# utrak.net
KiCad netlist of a schematic drawn in EAGLE
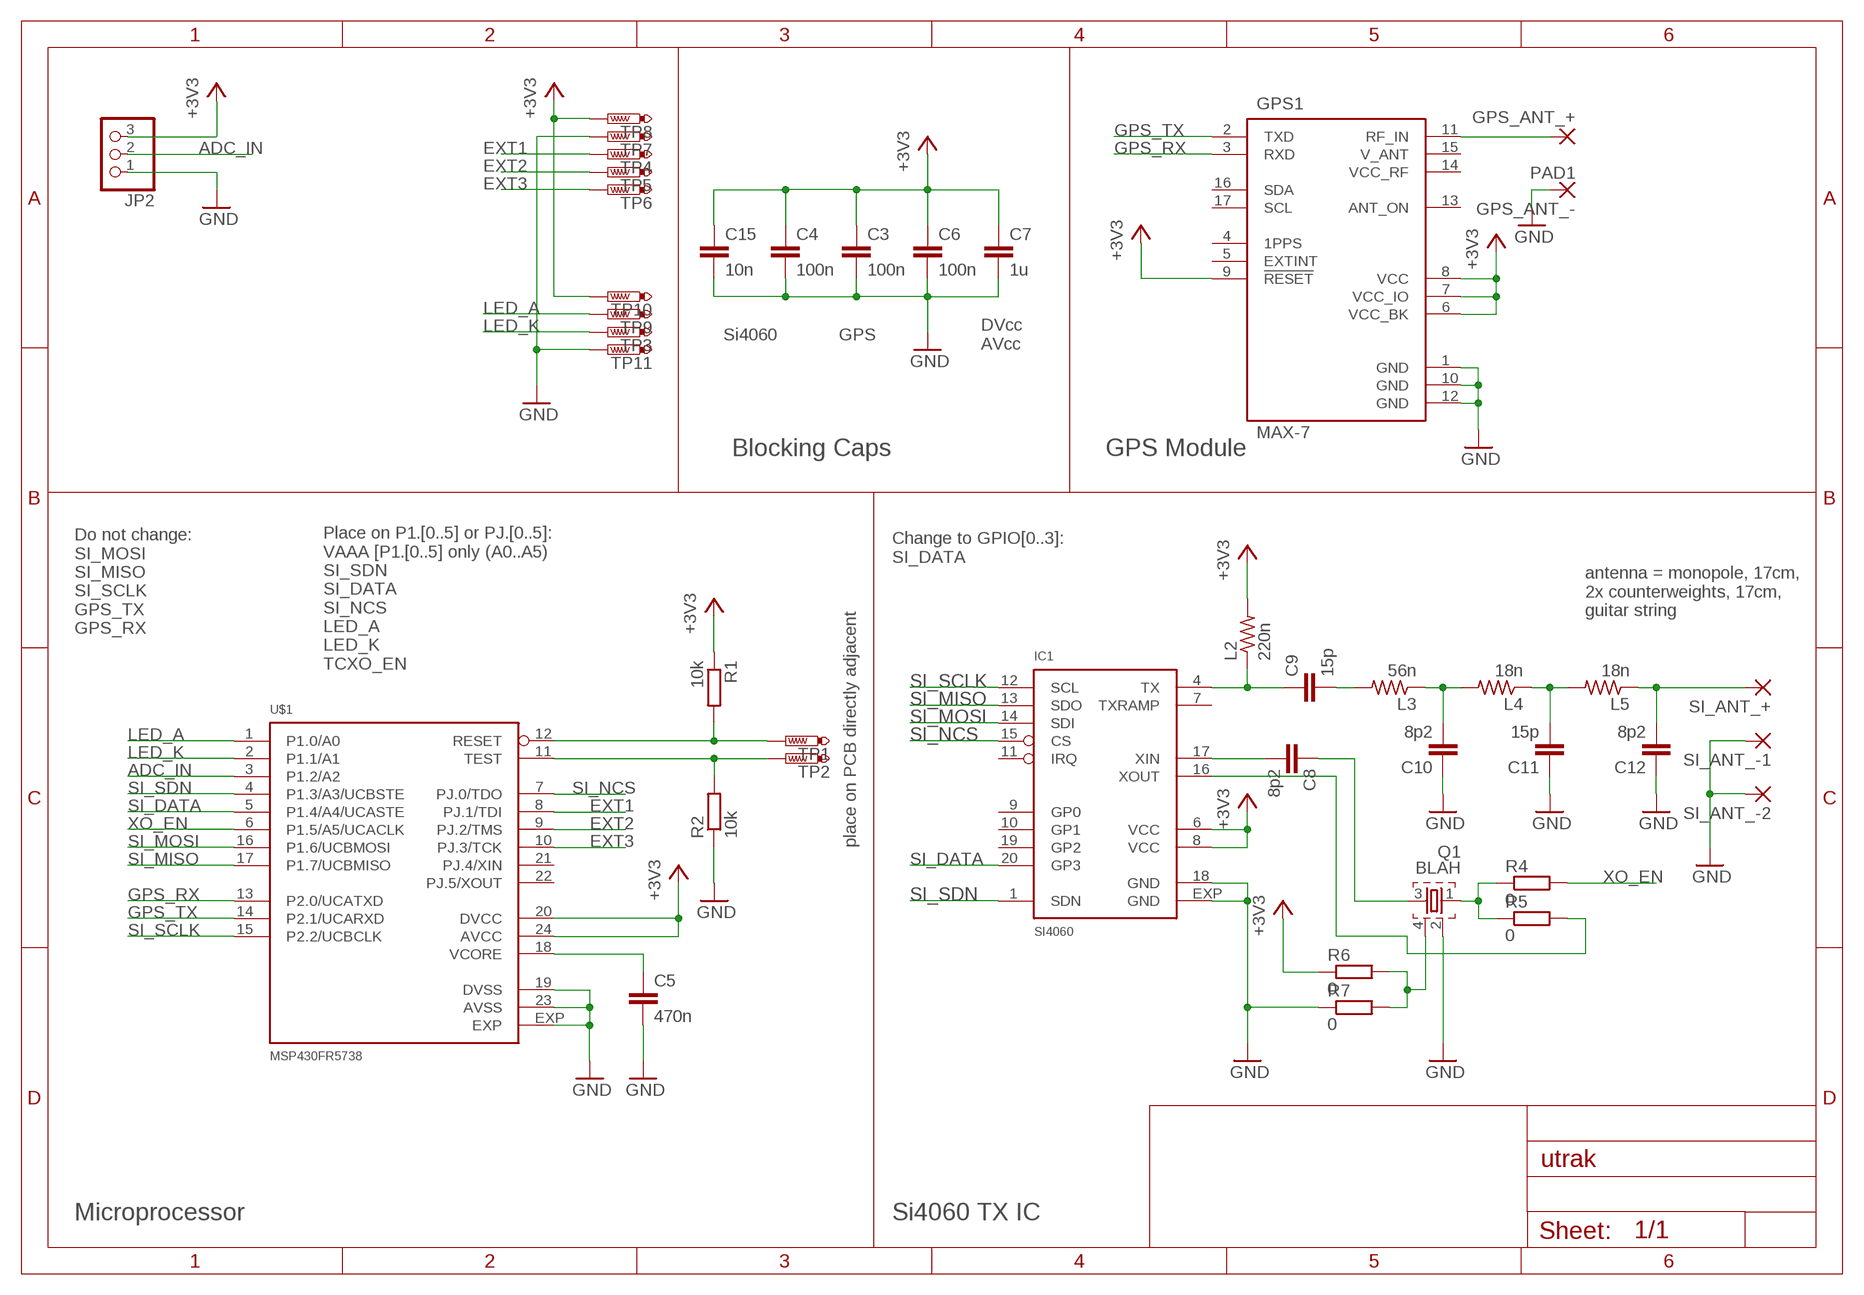
[diagram p0: schematic, sheet 1]

(export (version "E")
  (design (tool "Eeschema 10.0.6"))
  (components
    (comp (ref "C3")
      (value "100n")
      (footprint "eagle-import:C0603")
      (libsource (lib "eagle-import") (part "C-EUC0603"))
    )
    (comp (ref "C4")
      (value "100n")
      (footprint "eagle-import:C0603")
      (libsource (lib "eagle-import") (part "C-EUC0603"))
    )
    (comp (ref "C5")
      (value "470n")
      (footprint "eagle-import:C0805")
      (libsource (lib "eagle-import") (part "C-EUC0805"))
    )
    (comp (ref "C6")
      (value "100n")
      (footprint "eagle-import:C0603")
      (libsource (lib "eagle-import") (part "C-EUC0603"))
    )
    (comp (ref "C7")
      (value "1u")
      (footprint "eagle-import:C0603")
      (libsource (lib "eagle-import") (part "C-EUC0603"))
    )
    (comp (ref "C8")
      (value "8p2")
      (footprint "eagle-import:C0402")
      (libsource (lib "eagle-import") (part "C-EUC0402"))
    )
    (comp (ref "C9")
      (value "15p")
      (footprint "eagle-import:C0603")
      (libsource (lib "eagle-import") (part "C-EUC0603"))
    )
    (comp (ref "C10")
      (value "8p2")
      (footprint "eagle-import:C0603")
      (libsource (lib "eagle-import") (part "C-EUC0603"))
    )
    (comp (ref "C11")
      (value "15p")
      (footprint "eagle-import:C0603K")
      (libsource (lib "eagle-import") (part "C-EUC0603K"))
    )
    (comp (ref "C12")
      (value "8p2")
      (footprint "eagle-import:C0603")
      (libsource (lib "eagle-import") (part "C-EUC0603"))
    )
    (comp (ref "C15")
      (value "10n")
      (footprint "eagle-import:C0603")
      (libsource (lib "eagle-import") (part "C-EUC0603"))
    )
    (comp (ref "GPS1")
      (value "MAX-7")
      (footprint "eagle-import:UBLOX-7")
      (libsource (lib "eagle-import") (part "MAX-7"))
    )
    (comp (ref "GPS_ANT_+")
      (value "SMD2")
      (footprint "eagle-import:SMD1,27-2,54")
      (libsource (lib "eagle-import") (part "SMD2"))
    )
    (comp (ref "GPS_ANT_-")
      (value "PAD1")
      (footprint "eagle-import:SMD1,27-2,0")
      (libsource (lib "eagle-import") (part "PAD1"))
    )
    (comp (ref "IC1")
      (value "SI4060")
      (footprint "eagle-import:QFN20")
      (libsource (lib "eagle-import") (part "SI4060"))
    )
    (comp (ref "JP2")
      (value "PINHD-1X3")
      (footprint "eagle-import:1X03")
      (libsource (lib "eagle-import") (part "PINHD-1X3"))
    )
    (comp (ref "L2")
      (value "220n")
      (footprint "eagle-import:R0603")
      (libsource (lib "eagle-import") (part "R-US_R0603"))
    )
    (comp (ref "L3")
      (value "56n")
      (footprint "eagle-import:R0603")
      (libsource (lib "eagle-import") (part "R-US_R0603"))
    )
    (comp (ref "L4")
      (value "18n")
      (footprint "eagle-import:R0603")
      (libsource (lib "eagle-import") (part "R-US_R0603"))
    )
    (comp (ref "L5")
      (value "18n")
      (footprint "eagle-import:R0603")
      (libsource (lib "eagle-import") (part "R-US_R0603"))
    )
    (comp (ref "Q1")
      (value "BLAH")
      (footprint "eagle-import:CTS406")
      (libsource (lib "eagle-import") (part "BLAH"))
    )
    (comp (ref "R1")
      (value "10k")
      (footprint "eagle-import:R0402")
      (libsource (lib "eagle-import") (part "R-EU_R0402"))
    )
    (comp (ref "R2")
      (value "10k")
      (footprint "eagle-import:R0402")
      (libsource (lib "eagle-import") (part "R-EU_R0402"))
    )
    (comp (ref "R4")
      (value "0")
      (footprint "eagle-import:R0402")
      (libsource (lib "eagle-import") (part "R-EU_R0402"))
    )
    (comp (ref "R5")
      (value "0")
      (footprint "eagle-import:R0402")
      (libsource (lib "eagle-import") (part "R-EU_R0402"))
    )
    (comp (ref "R6")
      (value "0")
      (footprint "eagle-import:R0402")
      (libsource (lib "eagle-import") (part "R-EU_R0402"))
    )
    (comp (ref "R7")
      (value "0")
      (footprint "eagle-import:R0402")
      (libsource (lib "eagle-import") (part "R-EU_R0402"))
    )
    (comp (ref "SI_ANT_+")
      (value "SMD2")
      (footprint "eagle-import:SMD1,27-2,54")
      (libsource (lib "eagle-import") (part "SMD2"))
    )
    (comp (ref "SI_ANT_-1")
      (value "SMD2")
      (footprint "eagle-import:SMD1,27-2,54")
      (libsource (lib "eagle-import") (part "SMD2"))
    )
    (comp (ref "SI_ANT_-2")
      (value "SMD2")
      (footprint "eagle-import:SMD1,27-2,54")
      (libsource (lib "eagle-import") (part "SMD2"))
    )
    (comp (ref "TP1")
      (value "PTR1TP07R")
      (footprint "eagle-import:TP07R")
      (libsource (lib "eagle-import") (part "PTR1TP07R"))
    )
    (comp (ref "TP2")
      (value "PTR1TP07R")
      (footprint "eagle-import:TP07R")
      (libsource (lib "eagle-import") (part "PTR1TP07R"))
    )
    (comp (ref "TP3")
      (value "PTR1TP07R")
      (footprint "eagle-import:TP07R")
      (libsource (lib "eagle-import") (part "PTR1TP07R"))
    )
    (comp (ref "TP4")
      (value "PTR1TP07R")
      (footprint "eagle-import:TP07R")
      (libsource (lib "eagle-import") (part "PTR1TP07R"))
    )
    (comp (ref "TP5")
      (value "PTR1TP07R")
      (footprint "eagle-import:TP07R")
      (libsource (lib "eagle-import") (part "PTR1TP07R"))
    )
    (comp (ref "TP6")
      (value "PTR1TP07R")
      (footprint "eagle-import:TP07R")
      (libsource (lib "eagle-import") (part "PTR1TP07R"))
    )
    (comp (ref "TP7")
      (value "PTR1TP07R")
      (footprint "eagle-import:TP07R")
      (libsource (lib "eagle-import") (part "PTR1TP07R"))
    )
    (comp (ref "TP8")
      (value "PTR1TP07R")
      (footprint "eagle-import:TP07R")
      (libsource (lib "eagle-import") (part "PTR1TP07R"))
    )
    (comp (ref "TP9")
      (value "PTR1TP07R")
      (footprint "eagle-import:TP07R")
      (libsource (lib "eagle-import") (part "PTR1TP07R"))
    )
    (comp (ref "TP10")
      (value "PTR1TP07R")
      (footprint "eagle-import:TP07R")
      (libsource (lib "eagle-import") (part "PTR1TP07R"))
    )
    (comp (ref "TP11")
      (value "PTR1TP07R")
      (footprint "eagle-import:TP07R")
      (libsource (lib "eagle-import") (part "PTR1TP07R"))
    )
    (comp (ref "U$1")
      (value "MSP430FR5738")
      (footprint "eagle-import:QFN24-4X4")
      (libsource (lib "eagle-import") (part "MSP430FR5738"))
    )
  )
  (nets
    (net (code "1") (name "+3V3") (class "Default")
      (node (ref "C15") (pin "1") (pinfunction "1_1") (pintype "passive"))
      (node (ref "C3") (pin "1") (pinfunction "1_1") (pintype "passive"))
      (node (ref "C4") (pin "1") (pinfunction "1_1") (pintype "passive"))
      (node (ref "C6") (pin "1") (pinfunction "1_1") (pintype "passive"))
      (node (ref "C7") (pin "1") (pinfunction "1_1") (pintype "passive"))
      (node (ref "GPS1") (pin "6") (pinfunction "VCC_BK_6") (pintype "power_in"))
      (node (ref "GPS1") (pin "7") (pinfunction "VCC_IO_7") (pintype "power_in"))
      (node (ref "GPS1") (pin "8") (pinfunction "VCC_8") (pintype "power_in"))
      (node (ref "GPS1") (pin "9") (pinfunction "~{RESET}_9") (pintype "bidirectional"))
      (node (ref "IC1") (pin "6") (pinfunction "VCC_6") (pintype "power_in"))
      (node (ref "IC1") (pin "8") (pinfunction "VCC_8") (pintype "power_in"))
      (node (ref "JP2") (pin "3") (pinfunction "3_3") (pintype "passive"))
      (node (ref "L2") (pin "2") (pinfunction "2_2") (pintype "passive"))
      (node (ref "R1") (pin "1") (pinfunction "1_1") (pintype "passive"))
      (node (ref "R6") (pin "1") (pinfunction "1_1") (pintype "passive"))
      (node (ref "TP10") (pin "TP") (pinfunction "TP_TP") (pintype "input"))
      (node (ref "TP8") (pin "TP") (pinfunction "TP_TP") (pintype "input"))
      (node (ref "U$1") (pin "20") (pinfunction "DVCC_20") (pintype "power_in"))
      (node (ref "U$1") (pin "24") (pinfunction "AVCC_24") (pintype "power_in"))
    )
    (net (code "2") (name "/ADC_IN") (class "Default")
      (node (ref "JP2") (pin "2") (pinfunction "2_2") (pintype "passive"))
      (node (ref "U$1") (pin "3") (pinfunction "P1.2/A2_3") (pintype "bidirectional"))
    )
    (net (code "3") (name "/EXT1") (class "Default")
      (node (ref "TP4") (pin "TP") (pinfunction "TP_TP") (pintype "input"))
      (node (ref "U$1") (pin "8") (pinfunction "PJ.1/TDI_8") (pintype "bidirectional"))
    )
    (net (code "4") (name "/EXT2") (class "Default")
      (node (ref "TP5") (pin "TP") (pinfunction "TP_TP") (pintype "input"))
      (node (ref "U$1") (pin "9") (pinfunction "PJ.2/TMS_9") (pintype "bidirectional"))
    )
    (net (code "5") (name "/EXT3") (class "Default")
      (node (ref "TP6") (pin "TP") (pinfunction "TP_TP") (pintype "input"))
      (node (ref "U$1") (pin "10") (pinfunction "PJ.3/TCK_10") (pintype "bidirectional"))
    )
    (net (code "6") (name "/GPS_RX") (class "Default")
      (node (ref "GPS1") (pin "3") (pinfunction "RXD_3") (pintype "bidirectional"))
      (node (ref "U$1") (pin "13") (pinfunction "P2.0/UCATXD_13") (pintype "bidirectional"))
    )
    (net (code "7") (name "/GPS_TX") (class "Default")
      (node (ref "GPS1") (pin "2") (pinfunction "TXD_2") (pintype "bidirectional"))
      (node (ref "U$1") (pin "14") (pinfunction "P2.1/UCARXD_14") (pintype "bidirectional"))
    )
    (net (code "8") (name "/LED_A") (class "Default")
      (node (ref "TP9") (pin "TP") (pinfunction "TP_TP") (pintype "input"))
      (node (ref "U$1") (pin "1") (pinfunction "P1.0/A0_1") (pintype "bidirectional"))
    )
    (net (code "9") (name "/LED_K") (class "Default")
      (node (ref "TP3") (pin "TP") (pinfunction "TP_TP") (pintype "input"))
      (node (ref "U$1") (pin "2") (pinfunction "P1.1/A1_2") (pintype "bidirectional"))
    )
    (net (code "10") (name "/SI_DATA") (class "Default")
      (node (ref "IC1") (pin "20") (pinfunction "GP3_20") (pintype "bidirectional"))
      (node (ref "U$1") (pin "5") (pinfunction "P1.4/A4/UCASTE_5") (pintype "bidirectional"))
    )
    (net (code "11") (name "/SI_MISO") (class "Default")
      (node (ref "IC1") (pin "13") (pinfunction "SDO_13") (pintype "bidirectional"))
      (node (ref "U$1") (pin "17") (pinfunction "P1.7/UCBMISO_17") (pintype "bidirectional"))
    )
    (net (code "12") (name "/SI_MOSI") (class "Default")
      (node (ref "IC1") (pin "14") (pinfunction "SDI_14") (pintype "bidirectional"))
      (node (ref "U$1") (pin "16") (pinfunction "P1.6/UCBMOSI_16") (pintype "bidirectional"))
    )
    (net (code "13") (name "/SI_NCS") (class "Default")
      (node (ref "IC1") (pin "15") (pinfunction "CS_15") (pintype "bidirectional"))
      (node (ref "U$1") (pin "7") (pinfunction "PJ.0/TDO_7") (pintype "bidirectional"))
    )
    (net (code "14") (name "/SI_SCLK") (class "Default")
      (node (ref "IC1") (pin "12") (pinfunction "SCL_12") (pintype "bidirectional"))
      (node (ref "U$1") (pin "15") (pinfunction "P2.2/UCBCLK_15") (pintype "bidirectional"))
    )
    (net (code "15") (name "/SI_SDN") (class "Default")
      (node (ref "IC1") (pin "1") (pinfunction "SDN_1") (pintype "bidirectional"))
      (node (ref "U$1") (pin "4") (pinfunction "P1.3/A3/UCBSTE_4") (pintype "bidirectional"))
    )
    (net (code "16") (name "/XO_EN") (class "Default")
      (node (ref "R4") (pin "2") (pinfunction "2_2") (pintype "passive"))
      (node (ref "U$1") (pin "6") (pinfunction "P1.5/A5/UCACLK_6") (pintype "bidirectional"))
    )
    (net (code "17") (name "GND") (class "Default")
      (node (ref "C10") (pin "1") (pinfunction "1_1") (pintype "passive"))
      (node (ref "C11") (pin "1") (pinfunction "1_1") (pintype "passive"))
      (node (ref "C12") (pin "1") (pinfunction "1_1") (pintype "passive"))
      (node (ref "C15") (pin "2") (pinfunction "2_2") (pintype "passive"))
      (node (ref "C3") (pin "2") (pinfunction "2_2") (pintype "passive"))
      (node (ref "C4") (pin "2") (pinfunction "2_2") (pintype "passive"))
      (node (ref "C5") (pin "2") (pinfunction "2_2") (pintype "passive"))
      (node (ref "C6") (pin "2") (pinfunction "2_2") (pintype "passive"))
      (node (ref "C7") (pin "2") (pinfunction "2_2") (pintype "passive"))
      (node (ref "GPS1") (pin "1") (pinfunction "GND_1") (pintype "power_in"))
      (node (ref "GPS1") (pin "10") (pinfunction "GND_10") (pintype "power_in"))
      (node (ref "GPS1") (pin "12") (pinfunction "GND_12") (pintype "power_in"))
      (node (ref "GPS_ANT_-") (pin "P$1") (pinfunction "P_P$1") (pintype "passive"))
      (node (ref "IC1") (pin "18") (pinfunction "GND_18") (pintype "power_in"))
      (node (ref "IC1") (pin "EXP") (pinfunction "GND_EXP") (pintype "power_in"))
      (node (ref "JP2") (pin "1") (pinfunction "1_1") (pintype "passive"))
      (node (ref "Q1") (pin "2") (pinfunction "2_2") (pintype "passive"))
      (node (ref "R2") (pin "1") (pinfunction "1_1") (pintype "passive"))
      (node (ref "R7") (pin "1") (pinfunction "1_1") (pintype "passive"))
      (node (ref "SI_ANT_-1") (pin "1") (pinfunction "P_1") (pintype "passive"))
      (node (ref "SI_ANT_-2") (pin "1") (pinfunction "P_1") (pintype "passive"))
      (node (ref "TP11") (pin "TP") (pinfunction "TP_TP") (pintype "input"))
      (node (ref "TP7") (pin "TP") (pinfunction "TP_TP") (pintype "input"))
      (node (ref "U$1") (pin "19") (pinfunction "DVSS_19") (pintype "power_in"))
      (node (ref "U$1") (pin "23") (pinfunction "AVSS_23") (pintype "power_in"))
      (node (ref "U$1") (pin "EXP") (pinfunction "EXP_EXP") (pintype "power_in"))
    )
    (net (code "18") (name "Net-(C8-Pad1)") (class "Default")
      (node (ref "C8") (pin "1") (pinfunction "1_1") (pintype "passive"))
      (node (ref "Q1") (pin "3") (pinfunction "3_3") (pintype "passive"))
    )
    (net (code "19") (name "Net-(C9-Pad2)") (class "Default")
      (node (ref "C9") (pin "2") (pinfunction "2_2") (pintype "passive"))
      (node (ref "L3") (pin "2") (pinfunction "2_2") (pintype "passive"))
    )
    (net (code "20") (name "Net-(C10-Pad2)") (class "Default")
      (node (ref "C10") (pin "2") (pinfunction "2_2") (pintype "passive"))
      (node (ref "L3") (pin "1") (pinfunction "1_1") (pintype "passive"))
      (node (ref "L4") (pin "2") (pinfunction "2_2") (pintype "passive"))
    )
    (net (code "21") (name "Net-(C11-Pad2)") (class "Default")
      (node (ref "C11") (pin "2") (pinfunction "2_2") (pintype "passive"))
      (node (ref "L4") (pin "1") (pinfunction "1_1") (pintype "passive"))
      (node (ref "L5") (pin "2") (pinfunction "2_2") (pintype "passive"))
    )
    (net (code "22") (name "Net-(GPS1-RF_IN)") (class "Default")
      (node (ref "GPS1") (pin "11") (pinfunction "RF_IN_11") (pintype "bidirectional"))
      (node (ref "GPS_ANT_+") (pin "1") (pinfunction "P_1") (pintype "passive"))
    )
    (net (code "23") (name "Net-(IC1-TX)") (class "Default")
      (node (ref "C9") (pin "1") (pinfunction "1_1") (pintype "passive"))
      (node (ref "IC1") (pin "4") (pinfunction "TX_4") (pintype "bidirectional"))
      (node (ref "L2") (pin "1") (pinfunction "1_1") (pintype "passive"))
    )
    (net (code "24") (name "Net-(IC1-XIN)") (class "Default")
      (node (ref "C8") (pin "2") (pinfunction "2_2") (pintype "passive"))
      (node (ref "IC1") (pin "17") (pinfunction "XIN_17") (pintype "bidirectional"))
    )
    (net (code "25") (name "Net-(IC1-XOUT)") (class "Default")
      (node (ref "IC1") (pin "16") (pinfunction "XOUT_16") (pintype "bidirectional"))
      (node (ref "R5") (pin "2") (pinfunction "2_2") (pintype "passive"))
    )
    (net (code "26") (name "Net-(Q1-Pad1)") (class "Default")
      (node (ref "Q1") (pin "1") (pinfunction "1_1") (pintype "passive"))
      (node (ref "R4") (pin "1") (pinfunction "1_1") (pintype "passive"))
      (node (ref "R5") (pin "1") (pinfunction "1_1") (pintype "passive"))
    )
    (net (code "27") (name "Net-(Q1-Pad4)") (class "Default")
      (node (ref "Q1") (pin "4") (pinfunction "4_4") (pintype "passive"))
      (node (ref "R6") (pin "2") (pinfunction "2_2") (pintype "passive"))
      (node (ref "R7") (pin "2") (pinfunction "2_2") (pintype "passive"))
    )
    (net (code "28") (name "Net-(SI_ANT_+-P)") (class "Default")
      (node (ref "C12") (pin "2") (pinfunction "2_2") (pintype "passive"))
      (node (ref "L5") (pin "1") (pinfunction "1_1") (pintype "passive"))
      (node (ref "SI_ANT_+") (pin "1") (pinfunction "P_1") (pintype "passive"))
    )
    (net (code "29") (name "Net-(U$1-RESET)") (class "Default")
      (node (ref "R1") (pin "2") (pinfunction "2_2") (pintype "passive"))
      (node (ref "TP1") (pin "TP") (pinfunction "TP_TP") (pintype "input"))
      (node (ref "U$1") (pin "12") (pinfunction "RESET_12") (pintype "bidirectional"))
    )
    (net (code "30") (name "Net-(U$1-TEST)") (class "Default")
      (node (ref "R2") (pin "2") (pinfunction "2_2") (pintype "passive"))
      (node (ref "TP2") (pin "TP") (pinfunction "TP_TP") (pintype "input"))
      (node (ref "U$1") (pin "11") (pinfunction "TEST_11") (pintype "bidirectional"))
    )
    (net (code "31") (name "Net-(U$1-VCORE)") (class "Default")
      (node (ref "C5") (pin "1") (pinfunction "1_1") (pintype "passive"))
      (node (ref "U$1") (pin "18") (pinfunction "VCORE_18") (pintype "power_in"))
    )
    (net (code "32") (name "unconnected-(GPS1-1PPS-Pad4)") (class "Default")
      (node (ref "GPS1") (pin "4") (pinfunction "1PPS_4") (pintype "bidirectional"))
    )
    (net (code "33") (name "unconnected-(GPS1-ANT_ON-Pad13)") (class "Default")
      (node (ref "GPS1") (pin "13") (pinfunction "ANT_ON_13") (pintype "bidirectional"))
    )
    (net (code "34") (name "unconnected-(GPS1-EXTINT-Pad5)") (class "Default")
      (node (ref "GPS1") (pin "5") (pinfunction "EXTINT_5") (pintype "bidirectional"))
    )
    (net (code "35") (name "unconnected-(GPS1-SCL-Pad17)") (class "Default")
      (node (ref "GPS1") (pin "17") (pinfunction "SCL_17") (pintype "bidirectional"))
    )
    (net (code "36") (name "unconnected-(GPS1-SDA-Pad16)") (class "Default")
      (node (ref "GPS1") (pin "16") (pinfunction "SDA_16") (pintype "bidirectional"))
    )
    (net (code "37") (name "unconnected-(GPS1-VCC_RF-Pad14)") (class "Default")
      (node (ref "GPS1") (pin "14") (pinfunction "VCC_RF_14") (pintype "bidirectional"))
    )
    (net (code "38") (name "unconnected-(GPS1-V_ANT-Pad15)") (class "Default")
      (node (ref "GPS1") (pin "15") (pinfunction "V_ANT_15") (pintype "bidirectional"))
    )
    (net (code "39") (name "unconnected-(IC1-GP0-Pad9)") (class "Default")
      (node (ref "IC1") (pin "9") (pinfunction "GP0_9") (pintype "bidirectional"))
    )
    (net (code "40") (name "unconnected-(IC1-GP1-Pad10)") (class "Default")
      (node (ref "IC1") (pin "10") (pinfunction "GP1_10") (pintype "bidirectional"))
    )
    (net (code "41") (name "unconnected-(IC1-GP2-Pad19)") (class "Default")
      (node (ref "IC1") (pin "19") (pinfunction "GP2_19") (pintype "bidirectional"))
    )
    (net (code "42") (name "unconnected-(IC1-IRQ-Pad11)") (class "Default")
      (node (ref "IC1") (pin "11") (pinfunction "IRQ_11") (pintype "bidirectional"))
    )
    (net (code "43") (name "unconnected-(IC1-TXRAMP-Pad7)") (class "Default")
      (node (ref "IC1") (pin "7") (pinfunction "TXRAMP_7") (pintype "bidirectional"))
    )
    (net (code "44") (name "unconnected-(U$1-PJ.4{slash}XIN-Pad21)") (class "Default")
      (node (ref "U$1") (pin "21") (pinfunction "PJ.4/XIN_21") (pintype "bidirectional"))
    )
    (net (code "45") (name "unconnected-(U$1-PJ.5{slash}XOUT-Pad22)") (class "Default")
      (node (ref "U$1") (pin "22") (pinfunction "PJ.5/XOUT_22") (pintype "bidirectional"))
    )
  )
)
